# openrfid.net
KiCad netlist of a schematic drawn in EAGLE
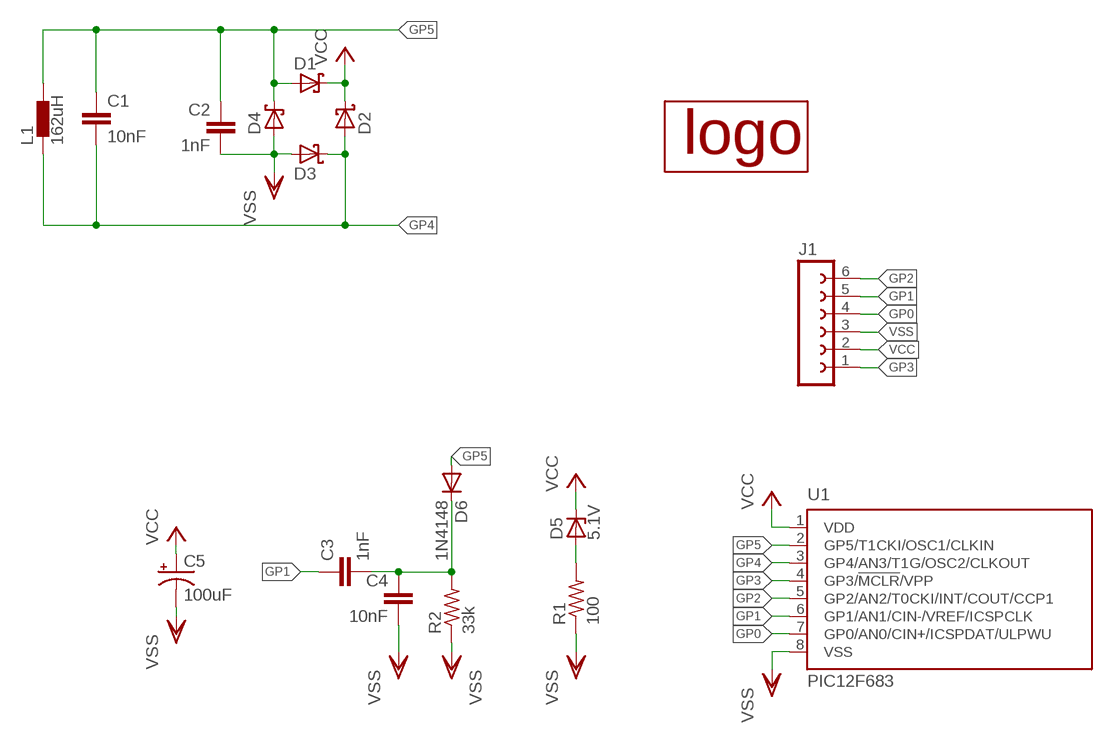
[diagram p0: schematic, sheet 1]

(export (version "E")
  (design (tool "Eeschema 10.0.6"))
  (components
    (comp (ref "C1")
      (value "10nF")
      (footprint "eagle-import:C050-024X044")
      (libsource (lib "eagle-import") (part "C-EU050-024X044"))
    )
    (comp (ref "C2")
      (value "1nF")
      (footprint "eagle-import:C025-024X044")
      (libsource (lib "eagle-import") (part "C-EU025-024X044"))
    )
    (comp (ref "C3")
      (value "1nF")
      (footprint "eagle-import:C025-024X044")
      (libsource (lib "eagle-import") (part "C-EU025-024X044"))
    )
    (comp (ref "C4")
      (value "10nF")
      (footprint "eagle-import:C050-024X044")
      (libsource (lib "eagle-import") (part "C-EU050-024X044"))
    )
    (comp (ref "C5")
      (value "100uF")
      (footprint "eagle-import:E2,5-6E")
      (libsource (lib "eagle-import") (part "CPOL-USE2,5-6E"))
    )
    (comp (ref "D1")
      (value "1N5817-B")
      (footprint "eagle-import:DO41-7.6")
      (libsource (lib "eagle-import") (part "1N5817-B"))
    )
    (comp (ref "D2")
      (value "1N5817-B")
      (footprint "eagle-import:DO41-7.6")
      (libsource (lib "eagle-import") (part "1N5817-B"))
    )
    (comp (ref "D3")
      (value "1N5817-B")
      (footprint "eagle-import:DO41-7.6")
      (libsource (lib "eagle-import") (part "1N5817-B"))
    )
    (comp (ref "D4")
      (value "1N5817-B")
      (footprint "eagle-import:DO41-7.6")
      (libsource (lib "eagle-import") (part "1N5817-B"))
    )
    (comp (ref "D5")
      (value "5.1V")
      (footprint "eagle-import:ZDIO-5")
      (libsource (lib "eagle-import") (part "ZENER-DIODEZD-5"))
    )
    (comp (ref "D6")
      (value "1N4148")
      (footprint "eagle-import:DO35-7")
      (libsource (lib "eagle-import") (part "1N4148DO35-7"))
    )
    (comp (ref "J1")
      (value "FE06-1")
      (footprint "eagle-import:FE06")
      (libsource (lib "eagle-import") (part "FE06-1"))
    )
    (comp (ref "L1")
      (value "162uH")
      (footprint "eagle-import:BL02RN2")
      (libsource (lib "eagle-import") (part "BL02RN2"))
    )
    (comp (ref "R1")
      (value "100")
      (footprint "eagle-import:0204_7")
      (libsource (lib "eagle-import") (part "R-US_0204/7"))
    )
    (comp (ref "R2")
      (value "33k")
      (footprint "eagle-import:0204_7")
      (libsource (lib "eagle-import") (part "R-US_0204/7"))
    )
    (comp (ref "U$1")
      (value "KBELOGO-SILK")
      (footprint "eagle-import:KBELOGO-SILK")
      (libsource (lib "eagle-import") (part "KBELOGO-SILK"))
    )
    (comp (ref "U1")
      (value "PIC12F683")
      (footprint "eagle-import:DIL8")
      (fields (field (name "MF") "MICROCHIP") (field (name "MPN") "PIC12F683-I/P"))
      (libsource (lib "eagle-import") (part "PIC12F683P"))
    )
  )
  (nets
    (net (code "1") (name "GP0") (class "Default")
      (node (ref "J1") (pin "4") (pinfunction "4_4") (pintype "passive"))
      (node (ref "U1") (pin "7") (pinfunction "GP0/AN0/CIN+/ICSPDAT/ULPWU_7") (pintype "bidirectional"))
    )
    (net (code "2") (name "GP1") (class "Default")
      (node (ref "C3") (pin "1") (pinfunction "1_1") (pintype "passive"))
      (node (ref "J1") (pin "5") (pinfunction "5_5") (pintype "passive"))
      (node (ref "U1") (pin "6") (pinfunction "GP1/AN1/CIN-/VREF/ICSPCLK_6") (pintype "bidirectional"))
    )
    (net (code "3") (name "GP2") (class "Default")
      (node (ref "J1") (pin "6") (pinfunction "6_6") (pintype "passive"))
      (node (ref "U1") (pin "5") (pinfunction "GP2/AN2/T0CKI/INT/COUT/CCP1_5") (pintype "bidirectional"))
    )
    (net (code "4") (name "GP3") (class "Default")
      (node (ref "J1") (pin "1") (pinfunction "1_1") (pintype "passive"))
      (node (ref "U1") (pin "4") (pinfunction "GP3/~{MCLR}/VPP_4") (pintype "bidirectional"))
    )
    (net (code "5") (name "GP4") (class "Default")
      (node (ref "C1") (pin "2") (pinfunction "2_2") (pintype "passive"))
      (node (ref "D2") (pin "A") (pinfunction "A_A") (pintype "passive"))
      (node (ref "D3") (pin "C") (pinfunction "C_C") (pintype "passive"))
      (node (ref "L1") (pin "1") (pinfunction "1_1") (pintype "passive"))
      (node (ref "U1") (pin "3") (pinfunction "GP4/AN3/T1G/OSC2/CLKOUT_3") (pintype "bidirectional"))
    )
    (net (code "6") (name "GP5") (class "Default")
      (node (ref "C1") (pin "1") (pinfunction "1_1") (pintype "passive"))
      (node (ref "C2") (pin "1") (pinfunction "1_1") (pintype "passive"))
      (node (ref "D1") (pin "A") (pinfunction "A_A") (pintype "passive"))
      (node (ref "D4") (pin "C") (pinfunction "C_C") (pintype "passive"))
      (node (ref "D6") (pin "A") (pinfunction "A_A") (pintype "passive"))
      (node (ref "L1") (pin "2") (pinfunction "2_2") (pintype "passive"))
      (node (ref "U1") (pin "2") (pinfunction "GP5/T1CKI/OSC1/CLKIN_2") (pintype "bidirectional"))
    )
    (net (code "7") (name "Net-(C3-Pad2)") (class "Default")
      (node (ref "C3") (pin "2") (pinfunction "2_2") (pintype "passive"))
      (node (ref "C4") (pin "1") (pinfunction "1_1") (pintype "passive"))
      (node (ref "D6") (pin "C") (pinfunction "C_C") (pintype "passive"))
      (node (ref "R2") (pin "2") (pinfunction "2_2") (pintype "passive"))
    )
    (net (code "8") (name "Net-(D5-PadA)") (class "Default")
      (node (ref "D5") (pin "A") (pinfunction "A_A") (pintype "passive"))
      (node (ref "R1") (pin "2") (pinfunction "2_2") (pintype "passive"))
    )
    (net (code "9") (name "VCC") (class "Default")
      (node (ref "C5") (pin "+") (pinfunction "+_+") (pintype "passive"))
      (node (ref "D1") (pin "C") (pinfunction "C_C") (pintype "passive"))
      (node (ref "D2") (pin "C") (pinfunction "C_C") (pintype "passive"))
      (node (ref "D5") (pin "C") (pinfunction "C_C") (pintype "passive"))
      (node (ref "J1") (pin "2") (pinfunction "2_2") (pintype "passive"))
      (node (ref "U1") (pin "1") (pinfunction "VDD_1") (pintype "power_in"))
    )
    (net (code "10") (name "VSS") (class "Default")
      (node (ref "C2") (pin "2") (pinfunction "2_2") (pintype "passive"))
      (node (ref "C4") (pin "2") (pinfunction "2_2") (pintype "passive"))
      (node (ref "C5") (pin "-") (pinfunction "-_-") (pintype "passive"))
      (node (ref "D3") (pin "A") (pinfunction "A_A") (pintype "passive"))
      (node (ref "D4") (pin "A") (pinfunction "A_A") (pintype "passive"))
      (node (ref "J1") (pin "3") (pinfunction "3_3") (pintype "passive"))
      (node (ref "R1") (pin "1") (pinfunction "1_1") (pintype "passive"))
      (node (ref "R2") (pin "1") (pinfunction "1_1") (pintype "passive"))
      (node (ref "U1") (pin "8") (pinfunction "VSS_8") (pintype "power_in"))
    )
  )
)
